# dtmf_rx.net
KiCad netlist of a schematic drawn in EAGLE
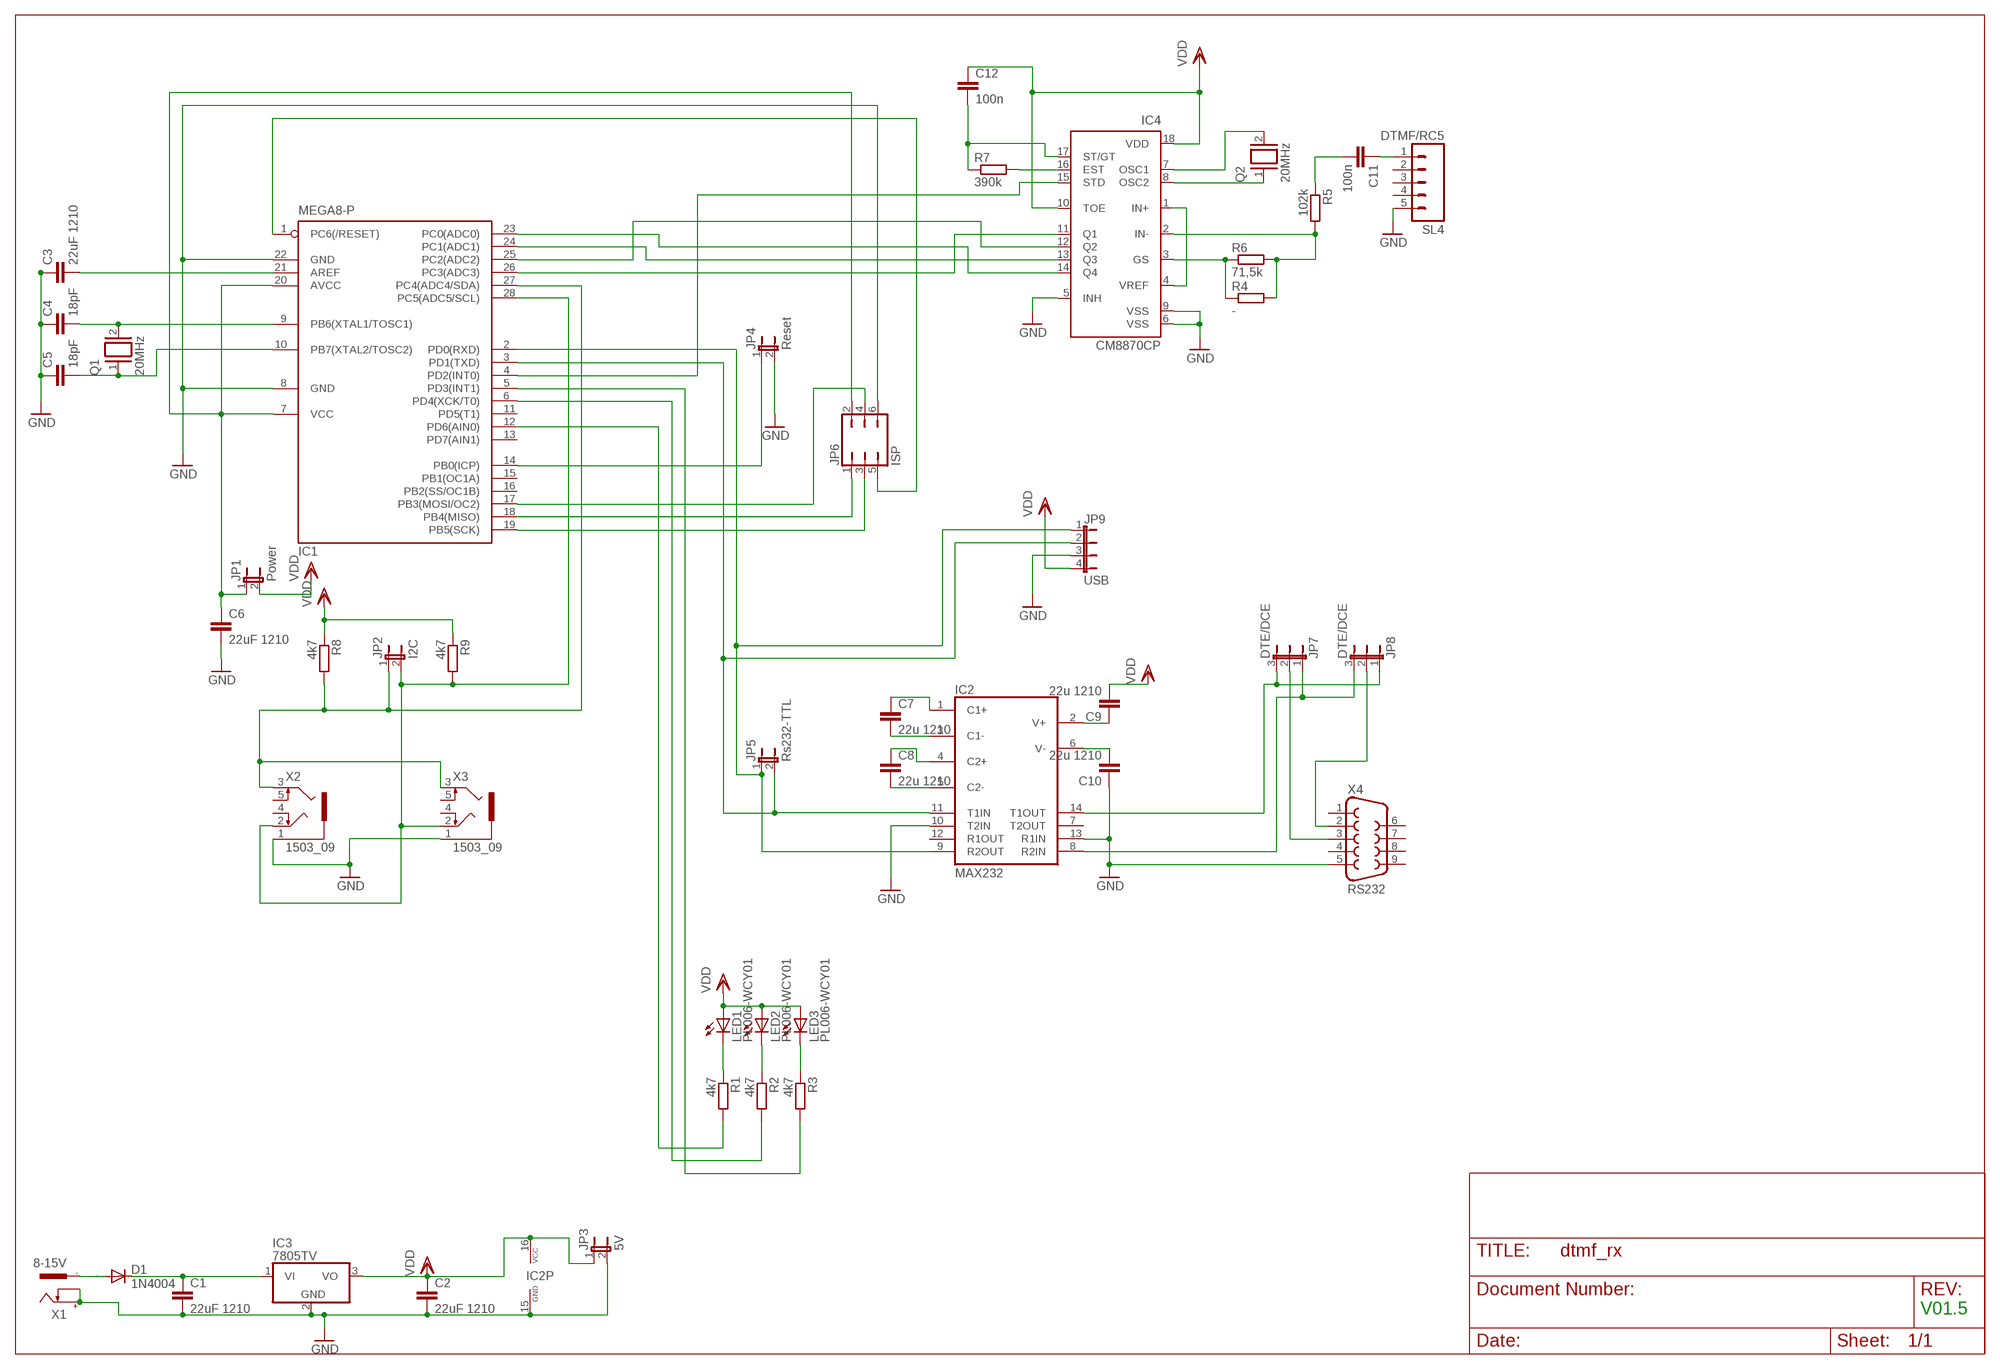
[diagram p0: schematic, sheet 1]

(export (version "E")
  (design (tool "Eeschema 10.0.6"))
  (components
    (comp (ref "C1")
      (value "22uF 1210")
      (footprint "eagle-import:C1206")
      (libsource (lib "eagle-import") (part "C-EUC1206"))
    )
    (comp (ref "C2")
      (value "22uF 1210")
      (footprint "eagle-import:C1206")
      (libsource (lib "eagle-import") (part "C-EUC1206"))
    )
    (comp (ref "C3")
      (value "22uF 1210")
      (footprint "eagle-import:C1206")
      (libsource (lib "eagle-import") (part "C-EUC1206"))
    )
    (comp (ref "C4")
      (value "18pF")
      (footprint "eagle-import:C025-025X050")
      (libsource (lib "eagle-import") (part "resistor_C-EU025-025X050"))
    )
    (comp (ref "C5")
      (value "18pF")
      (footprint "eagle-import:C025-025X050")
      (libsource (lib "eagle-import") (part "resistor_C-EU025-025X050"))
    )
    (comp (ref "C6")
      (value "22uF 1210")
      (footprint "eagle-import:C1206")
      (libsource (lib "eagle-import") (part "C-EUC1206"))
    )
    (comp (ref "C7")
      (value "22u 1210")
      (footprint "eagle-import:C1206")
      (libsource (lib "eagle-import") (part "C-EUC1206"))
    )
    (comp (ref "C8")
      (value "22u 1210")
      (footprint "eagle-import:C1206")
      (libsource (lib "eagle-import") (part "C-EUC1206"))
    )
    (comp (ref "C9")
      (value "22u 1210")
      (footprint "eagle-import:C1206")
      (libsource (lib "eagle-import") (part "C-EUC1206"))
    )
    (comp (ref "C10")
      (value "22u 1210")
      (footprint "eagle-import:C1206")
      (libsource (lib "eagle-import") (part "C-EUC1206"))
    )
    (comp (ref "C11")
      (value "100n")
      (footprint "eagle-import:C050-025X075")
      (libsource (lib "eagle-import") (part "C-EU050-025X075"))
    )
    (comp (ref "C12")
      (value "100n")
      (footprint "eagle-import:C050-025X075")
      (libsource (lib "eagle-import") (part "C-EU050-025X075"))
    )
    (comp (ref "D1")
      (value "1N4004")
      (footprint "eagle-import:DO41-10")
      (libsource (lib "eagle-import") (part "1N4004"))
    )
    (comp (ref "IC1")
      (value "MEGA8-P")
      (footprint "eagle-import:DIL28-3")
      (libsource (lib "eagle-import") (part "MEGA8-P"))
    )
    (comp (ref "IC2")
      (value "MAX232")
      (footprint "eagle-import:DIL16")
      (fields (field (name "MF") "MAXIM") (field (name "MPN") "MAX232ACPE+"))
      (libsource (lib "eagle-import") (part "MAX232"))
    )
    (comp (ref "IC3")
      (value "7805TV")
      (footprint "eagle-import:TO220V")
      (libsource (lib "eagle-import") (part "78TV05"))
    )
    (comp (ref "IC4")
      (value "CM8870CP")
      (footprint "eagle-import:DIL18")
      (libsource (lib "eagle-import") (part "CM8870CP"))
    )
    (comp (ref "JP1")
      (value "Power")
      (footprint "eagle-import:JP1")
      (libsource (lib "eagle-import") (part "JP1E"))
    )
    (comp (ref "JP2")
      (value "I2C")
      (footprint "eagle-import:JP1")
      (libsource (lib "eagle-import") (part "JP1E"))
    )
    (comp (ref "JP3")
      (value "5V")
      (footprint "eagle-import:JP1")
      (libsource (lib "eagle-import") (part "JP1E"))
    )
    (comp (ref "JP4")
      (value "Reset")
      (footprint "eagle-import:JP1")
      (libsource (lib "eagle-import") (part "JP1E"))
    )
    (comp (ref "JP5")
      (value "Rs232-TTL")
      (footprint "eagle-import:JP1")
      (libsource (lib "eagle-import") (part "JP1E"))
    )
    (comp (ref "JP6")
      (value "ISP")
      (footprint "eagle-import:JP3Q")
      (libsource (lib "eagle-import") (part "JP3Q"))
    )
    (comp (ref "JP7")
      (value "DTE/DCE")
      (footprint "eagle-import:JP2")
      (libsource (lib "eagle-import") (part "JP2E"))
    )
    (comp (ref "JP8")
      (value "DTE/DCE")
      (footprint "eagle-import:JP2")
      (libsource (lib "eagle-import") (part "JP2E"))
    )
    (comp (ref "JP9")
      (value "USB")
      (footprint "eagle-import:JP4")
      (libsource (lib "eagle-import") (part "JP4E"))
    )
    (comp (ref "LED1")
      (value "PL006-WCY01")
      (footprint "eagle-import:SOT23")
      (libsource (lib "eagle-import") (part "PL006-WCY01"))
    )
    (comp (ref "LED2")
      (value "PL006-WCY01")
      (footprint "eagle-import:SOT23")
      (libsource (lib "eagle-import") (part "PL006-WCY01"))
    )
    (comp (ref "LED3")
      (value "PL006-WCY01")
      (footprint "eagle-import:SOT23")
      (libsource (lib "eagle-import") (part "PL006-WCY01"))
    )
    (comp (ref "Q1")
      (value "20MHz")
      (footprint "eagle-import:QS")
      (libsource (lib "eagle-import") (part "XTAL/S"))
    )
    (comp (ref "Q2")
      (value "20MHz")
      (footprint "eagle-import:QS")
      (libsource (lib "eagle-import") (part "XTAL/S"))
    )
    (comp (ref "R1")
      (value "4k7")
      (footprint "eagle-import:0207_5V")
      (libsource (lib "eagle-import") (part "R-EU_0207/5V"))
    )
    (comp (ref "R2")
      (value "4k7")
      (footprint "eagle-import:0207_5V")
      (libsource (lib "eagle-import") (part "R-EU_0207/5V"))
    )
    (comp (ref "R3")
      (value "4k7")
      (footprint "eagle-import:0207_5V")
      (libsource (lib "eagle-import") (part "R-EU_0207/5V"))
    )
    (comp (ref "R4")
      (value "-")
      (footprint "eagle-import:0207_5V")
      (libsource (lib "eagle-import") (part "R-EU_0207/5V"))
    )
    (comp (ref "R5")
      (value "102k")
      (footprint "eagle-import:0207_5V")
      (libsource (lib "eagle-import") (part "R-EU_0207/5V"))
    )
    (comp (ref "R6")
      (value "71,5k")
      (footprint "eagle-import:0207_5V")
      (libsource (lib "eagle-import") (part "R-EU_0207/5V"))
    )
    (comp (ref "R7")
      (value "390k")
      (footprint "eagle-import:0207_5V")
      (libsource (lib "eagle-import") (part "R-EU_0207/5V"))
    )
    (comp (ref "R8")
      (value "4k7")
      (footprint "eagle-import:0207_5V")
      (libsource (lib "eagle-import") (part "R-EU_0207/5V"))
    )
    (comp (ref "R9")
      (value "4k7")
      (footprint "eagle-import:0207_5V")
      (libsource (lib "eagle-import") (part "R-EU_0207/5V"))
    )
    (comp (ref "SL4")
      (value "DTMF/RC5")
      (footprint "eagle-import:05P")
      (libsource (lib "eagle-import") (part "M05"))
    )
    (comp (ref "X1")
      (value "8-15V")
      (footprint "eagle-import:737992-5")
      (libsource (lib "eagle-import") (part "737992-55"))
    )
    (comp (ref "X2")
      (value "1503_09")
      (footprint "eagle-import:1503_09")
      (libsource (lib "eagle-import") (part "1503_09"))
    )
    (comp (ref "X3")
      (value "1503_09")
      (footprint "eagle-import:1503_09")
      (libsource (lib "eagle-import") (part "1503_09"))
    )
    (comp (ref "X4")
      (value "RS232")
      (footprint "eagle-import:F09H")
      (libsource (lib "eagle-import") (part "F09H"))
    )
  )
  (nets
    (net (code "1") (name "GND") (class "Default")
      (node (ref "C1") (pin "2") (pinfunction "2_2") (pintype "passive"))
      (node (ref "C10") (pin "1") (pinfunction "1_1") (pintype "passive"))
      (node (ref "C2") (pin "2") (pinfunction "2_2") (pintype "passive"))
      (node (ref "C3") (pin "1") (pinfunction "1_1") (pintype "passive"))
      (node (ref "C4") (pin "1") (pinfunction "1_1") (pintype "passive"))
      (node (ref "C5") (pin "1") (pinfunction "1_1") (pintype "passive"))
      (node (ref "C6") (pin "2") (pinfunction "2_2") (pintype "passive"))
      (node (ref "IC1") (pin "22") (pinfunction "GND_22") (pintype "power_in"))
      (node (ref "IC1") (pin "8") (pinfunction "GND_8") (pintype "power_in"))
      (node (ref "IC2") (pin "10") (pinfunction "T2IN_10") (pintype "input"))
      (node (ref "IC2") (pin "13") (pinfunction "R1IN_13") (pintype "input"))
      (node (ref "IC2") (pin "15") (pinfunction "GND_15") (pintype "power_in"))
      (node (ref "IC3") (pin "2") (pinfunction "GND_2") (pintype "passive"))
      (node (ref "IC4") (pin "5") (pinfunction "INH_5") (pintype "input"))
      (node (ref "IC4") (pin "6") (pinfunction "VSS_6") (pintype "power_in"))
      (node (ref "IC4") (pin "9") (pinfunction "VSS_9") (pintype "power_in"))
      (node (ref "JP3") (pin "2") (pinfunction "2_2") (pintype "passive"))
      (node (ref "JP4") (pin "2") (pinfunction "2_2") (pintype "passive"))
      (node (ref "JP6") (pin "6") (pinfunction "6_6") (pintype "passive"))
      (node (ref "JP9") (pin "3") (pinfunction "3_3") (pintype "passive"))
      (node (ref "SL4") (pin "5") (pinfunction "5_5") (pintype "passive"))
      (node (ref "X1") (pin "+") (pinfunction "+_+") (pintype "passive"))
      (node (ref "X1") (pin "K") (pinfunction "K_K") (pintype "passive"))
      (node (ref "X2") (pin "1") (pinfunction "1_1") (pintype "passive"))
      (node (ref "X3") (pin "1") (pinfunction "1_1") (pintype "passive"))
      (node (ref "X4") (pin "5") (pinfunction "5_5") (pintype "passive"))
    )
    (net (code "2") (name "Net-(C11-Pad1)") (class "Default")
      (node (ref "C11") (pin "1") (pinfunction "1_1") (pintype "passive"))
      (node (ref "SL4") (pin "1") (pinfunction "1_1") (pintype "passive"))
    )
    (net (code "3") (name "Net-(C11-Pad2)") (class "Default")
      (node (ref "C11") (pin "2") (pinfunction "2_2") (pintype "passive"))
      (node (ref "R5") (pin "1") (pinfunction "1_1") (pintype "passive"))
    )
    (net (code "4") (name "Net-(D1-PadA)") (class "Default")
      (node (ref "D1") (pin "A") (pinfunction "A_A") (pintype "passive"))
      (node (ref "X1") (pin "-1") (pinfunction "-1_-1") (pintype "passive"))
    )
    (net (code "5") (name "Net-(IC1-AREF)") (class "Default")
      (node (ref "C3") (pin "2") (pinfunction "2_2") (pintype "passive"))
      (node (ref "IC1") (pin "21") (pinfunction "AREF_21") (pintype "passive"))
    )
    (net (code "6") (name "Net-(IC1-AVCC)") (class "Default")
      (node (ref "C6") (pin "1") (pinfunction "1_1") (pintype "passive"))
      (node (ref "IC1") (pin "20") (pinfunction "AVCC_20") (pintype "power_in"))
      (node (ref "IC1") (pin "7") (pinfunction "VCC_7") (pintype "power_in"))
      (node (ref "JP1") (pin "1") (pinfunction "1_1") (pintype "passive"))
      (node (ref "JP6") (pin "2") (pinfunction "2_2") (pintype "passive"))
    )
    (net (code "7") (name "Net-(IC1-PB0(ICP))") (class "Default")
      (node (ref "IC1") (pin "14") (pinfunction "PB0(ICP)_14") (pintype "bidirectional"))
      (node (ref "JP4") (pin "1") (pinfunction "1_1") (pintype "passive"))
    )
    (net (code "8") (name "Net-(IC1-PB3(MOSI{slash}OC2))") (class "Default")
      (node (ref "IC1") (pin "17") (pinfunction "PB3(MOSI/OC2)_17") (pintype "bidirectional"))
      (node (ref "JP6") (pin "4") (pinfunction "4_4") (pintype "passive"))
    )
    (net (code "9") (name "Net-(IC1-PB4(MISO))") (class "Default")
      (node (ref "IC1") (pin "18") (pinfunction "PB4(MISO)_18") (pintype "bidirectional"))
      (node (ref "JP6") (pin "1") (pinfunction "1_1") (pintype "passive"))
    )
    (net (code "10") (name "Net-(IC1-PB5(SCK))") (class "Default")
      (node (ref "IC1") (pin "19") (pinfunction "PB5(SCK)_19") (pintype "bidirectional"))
      (node (ref "JP6") (pin "3") (pinfunction "3_3") (pintype "passive"))
    )
    (net (code "11") (name "Net-(IC1-PB6(XTAL1{slash}TOSC1))") (class "Default")
      (node (ref "C4") (pin "2") (pinfunction "2_2") (pintype "passive"))
      (node (ref "IC1") (pin "9") (pinfunction "PB6(XTAL1/TOSC1)_9") (pintype "bidirectional"))
      (node (ref "Q1") (pin "2") (pinfunction "2_2") (pintype "passive"))
    )
    (net (code "12") (name "Net-(IC1-PB7(XTAL2{slash}TOSC2))") (class "Default")
      (node (ref "C5") (pin "2") (pinfunction "2_2") (pintype "passive"))
      (node (ref "IC1") (pin "10") (pinfunction "PB7(XTAL2/TOSC2)_10") (pintype "bidirectional"))
      (node (ref "Q1") (pin "1") (pinfunction "1_1") (pintype "passive"))
    )
    (net (code "13") (name "Net-(IC1-PC0(ADC0))") (class "Default")
      (node (ref "IC1") (pin "23") (pinfunction "PC0(ADC0)_23") (pintype "bidirectional"))
      (node (ref "IC4") (pin "14") (pinfunction "Q4_14") (pintype "output"))
    )
    (net (code "14") (name "Net-(IC1-PC1(ADC1))") (class "Default")
      (node (ref "IC1") (pin "24") (pinfunction "PC1(ADC1)_24") (pintype "bidirectional"))
      (node (ref "IC4") (pin "13") (pinfunction "Q3_13") (pintype "output"))
    )
    (net (code "15") (name "Net-(IC1-PC2(ADC2))") (class "Default")
      (node (ref "IC1") (pin "25") (pinfunction "PC2(ADC2)_25") (pintype "bidirectional"))
      (node (ref "IC4") (pin "12") (pinfunction "Q2_12") (pintype "output"))
    )
    (net (code "16") (name "Net-(IC1-PC3(ADC3))") (class "Default")
      (node (ref "IC1") (pin "26") (pinfunction "PC3(ADC3)_26") (pintype "bidirectional"))
      (node (ref "IC4") (pin "11") (pinfunction "Q1_11") (pintype "output"))
    )
    (net (code "17") (name "Net-(IC1-PC4(ADC4{slash}SDA))") (class "Default")
      (node (ref "IC1") (pin "27") (pinfunction "PC4(ADC4/SDA)_27") (pintype "bidirectional"))
      (node (ref "JP2") (pin "1") (pinfunction "1_1") (pintype "passive"))
      (node (ref "R8") (pin "2") (pinfunction "2_2") (pintype "passive"))
      (node (ref "X2") (pin "3") (pinfunction "3_3") (pintype "passive"))
      (node (ref "X3") (pin "3") (pinfunction "3_3") (pintype "passive"))
    )
    (net (code "18") (name "Net-(IC1-PC5(ADC5{slash}SCL))") (class "Default")
      (node (ref "IC1") (pin "28") (pinfunction "PC5(ADC5/SCL)_28") (pintype "bidirectional"))
      (node (ref "JP2") (pin "2") (pinfunction "2_2") (pintype "passive"))
      (node (ref "R9") (pin "2") (pinfunction "2_2") (pintype "passive"))
      (node (ref "X2") (pin "2") (pinfunction "2_2") (pintype "passive"))
      (node (ref "X3") (pin "2") (pinfunction "2_2") (pintype "passive"))
    )
    (net (code "19") (name "Net-(IC1-PC6({slash}RESET))") (class "Default")
      (node (ref "IC1") (pin "1") (pinfunction "PC6(/RESET)_1") (pintype "bidirectional"))
      (node (ref "JP6") (pin "5") (pinfunction "5_5") (pintype "passive"))
    )
    (net (code "20") (name "Net-(IC1-PD0(RXD))") (class "Default")
      (node (ref "IC1") (pin "2") (pinfunction "PD0(RXD)_2") (pintype "bidirectional"))
      (node (ref "IC2") (pin "9") (pinfunction "R2OUT_9") (pintype "output"))
      (node (ref "JP5") (pin "1") (pinfunction "1_1") (pintype "passive"))
      (node (ref "JP9") (pin "1") (pinfunction "1_1") (pintype "passive"))
    )
    (net (code "21") (name "Net-(IC1-PD1(TXD))") (class "Default")
      (node (ref "IC1") (pin "3") (pinfunction "PD1(TXD)_3") (pintype "bidirectional"))
      (node (ref "IC2") (pin "11") (pinfunction "T1IN_11") (pintype "input"))
      (node (ref "JP5") (pin "2") (pinfunction "2_2") (pintype "passive"))
      (node (ref "JP9") (pin "2") (pinfunction "2_2") (pintype "passive"))
    )
    (net (code "22") (name "Net-(IC1-PD2(INT0))") (class "Default")
      (node (ref "IC1") (pin "4") (pinfunction "PD2(INT0)_4") (pintype "bidirectional"))
      (node (ref "IC4") (pin "15") (pinfunction "STD_15") (pintype "input"))
    )
    (net (code "23") (name "Net-(IC1-PD3(INT1))") (class "Default")
      (node (ref "IC1") (pin "5") (pinfunction "PD3(INT1)_5") (pintype "bidirectional"))
      (node (ref "R3") (pin "2") (pinfunction "2_2") (pintype "passive"))
    )
    (net (code "24") (name "Net-(IC1-PD4(XCK{slash}T0))") (class "Default")
      (node (ref "IC1") (pin "6") (pinfunction "PD4(XCK/T0)_6") (pintype "bidirectional"))
      (node (ref "R2") (pin "2") (pinfunction "2_2") (pintype "passive"))
    )
    (net (code "25") (name "Net-(IC1-PD6(AIN0))") (class "Default")
      (node (ref "IC1") (pin "12") (pinfunction "PD6(AIN0)_12") (pintype "bidirectional"))
      (node (ref "R1") (pin "2") (pinfunction "2_2") (pintype "passive"))
    )
    (net (code "26") (name "Net-(IC2A-C1+)") (class "Default")
      (node (ref "C7") (pin "1") (pinfunction "1_1") (pintype "passive"))
      (node (ref "IC2") (pin "1") (pinfunction "C1+_1") (pintype "bidirectional"))
    )
    (net (code "27") (name "Net-(IC2A-C1-)") (class "Default")
      (node (ref "C7") (pin "2") (pinfunction "2_2") (pintype "passive"))
      (node (ref "IC2") (pin "3") (pinfunction "C1-_3") (pintype "bidirectional"))
    )
    (net (code "28") (name "Net-(IC2A-C2+)") (class "Default")
      (node (ref "C8") (pin "1") (pinfunction "1_1") (pintype "passive"))
      (node (ref "IC2") (pin "4") (pinfunction "C2+_4") (pintype "bidirectional"))
    )
    (net (code "29") (name "Net-(IC2A-C2-)") (class "Default")
      (node (ref "C8") (pin "2") (pinfunction "2_2") (pintype "passive"))
      (node (ref "IC2") (pin "5") (pinfunction "C2-_5") (pintype "bidirectional"))
    )
    (net (code "30") (name "Net-(IC2A-R2IN)") (class "Default")
      (node (ref "IC2") (pin "8") (pinfunction "R2IN_8") (pintype "input"))
      (node (ref "JP7") (pin "1") (pinfunction "1_1") (pintype "passive"))
      (node (ref "JP8") (pin "3") (pinfunction "3_3") (pintype "passive"))
    )
    (net (code "31") (name "Net-(IC2A-T1OUT)") (class "Default")
      (node (ref "IC2") (pin "14") (pinfunction "T1OUT_14") (pintype "output"))
      (node (ref "JP7") (pin "3") (pinfunction "3_3") (pintype "passive"))
      (node (ref "JP8") (pin "1") (pinfunction "1_1") (pintype "passive"))
    )
    (net (code "32") (name "Net-(IC2A-V+)") (class "Default")
      (node (ref "C9") (pin "1") (pinfunction "1_1") (pintype "passive"))
      (node (ref "IC2") (pin "2") (pinfunction "V+_2") (pintype "bidirectional"))
    )
    (net (code "33") (name "Net-(IC2A-V-)") (class "Default")
      (node (ref "C10") (pin "2") (pinfunction "2_2") (pintype "passive"))
      (node (ref "IC2") (pin "6") (pinfunction "V-_6") (pintype "bidirectional"))
    )
    (net (code "34") (name "Net-(IC3-VI)") (class "Default")
      (node (ref "C1") (pin "1") (pinfunction "1_1") (pintype "passive"))
      (node (ref "D1") (pin "C") (pinfunction "C_C") (pintype "passive"))
      (node (ref "IC3") (pin "1") (pinfunction "VI_1") (pintype "input"))
    )
    (net (code "35") (name "Net-(IC4-EST)") (class "Default")
      (node (ref "IC4") (pin "16") (pinfunction "EST_16") (pintype "input"))
      (node (ref "R7") (pin "2") (pinfunction "2_2") (pintype "passive"))
    )
    (net (code "36") (name "Net-(IC4-GS)") (class "Default")
      (node (ref "IC4") (pin "3") (pinfunction "GS_3") (pintype "input"))
      (node (ref "R4") (pin "1") (pinfunction "1_1") (pintype "passive"))
      (node (ref "R6") (pin "1") (pinfunction "1_1") (pintype "passive"))
    )
    (net (code "37") (name "Net-(IC4-IN+)") (class "Default")
      (node (ref "IC4") (pin "1") (pinfunction "IN+_1") (pintype "input"))
      (node (ref "IC4") (pin "4") (pinfunction "VREF_4") (pintype "output"))
    )
    (net (code "38") (name "Net-(IC4-IN-)") (class "Default")
      (node (ref "IC4") (pin "2") (pinfunction "IN-_2") (pintype "input"))
      (node (ref "R4") (pin "2") (pinfunction "2_2") (pintype "passive"))
      (node (ref "R5") (pin "2") (pinfunction "2_2") (pintype "passive"))
      (node (ref "R6") (pin "2") (pinfunction "2_2") (pintype "passive"))
    )
    (net (code "39") (name "Net-(IC4-OSC1)") (class "Default")
      (node (ref "IC4") (pin "7") (pinfunction "OSC1_7") (pintype "input"))
      (node (ref "Q2") (pin "2") (pinfunction "2_2") (pintype "passive"))
    )
    (net (code "40") (name "Net-(IC4-OSC2)") (class "Default")
      (node (ref "IC4") (pin "8") (pinfunction "OSC2_8") (pintype "bidirectional"))
      (node (ref "Q2") (pin "1") (pinfunction "1_1") (pintype "passive"))
    )
    (net (code "41") (name "Net-(IC4-ST{slash}GT)") (class "Default")
      (node (ref "C12") (pin "2") (pinfunction "2_2") (pintype "passive"))
      (node (ref "IC4") (pin "17") (pinfunction "ST/GT_17") (pintype "bidirectional"))
      (node (ref "R7") (pin "1") (pinfunction "1_1") (pintype "passive"))
    )
    (net (code "42") (name "Net-(JP7-Pad2)") (class "Default")
      (node (ref "JP7") (pin "2") (pinfunction "2_2") (pintype "passive"))
      (node (ref "X4") (pin "3") (pinfunction "3_3") (pintype "passive"))
    )
    (net (code "43") (name "Net-(JP8-Pad2)") (class "Default")
      (node (ref "JP8") (pin "2") (pinfunction "2_2") (pintype "passive"))
      (node (ref "X4") (pin "2") (pinfunction "2_2") (pintype "passive"))
    )
    (net (code "44") (name "Net-(LED1-C)") (class "Default")
      (node (ref "LED1") (pin "3") (pinfunction "C_3") (pintype "passive"))
      (node (ref "R1") (pin "1") (pinfunction "1_1") (pintype "passive"))
    )
    (net (code "45") (name "Net-(LED2-C)") (class "Default")
      (node (ref "LED2") (pin "3") (pinfunction "C_3") (pintype "passive"))
      (node (ref "R2") (pin "1") (pinfunction "1_1") (pintype "passive"))
    )
    (net (code "46") (name "Net-(LED3-C)") (class "Default")
      (node (ref "LED3") (pin "3") (pinfunction "C_3") (pintype "passive"))
      (node (ref "R3") (pin "1") (pinfunction "1_1") (pintype "passive"))
    )
    (net (code "47") (name "VDD") (class "Default")
      (node (ref "C12") (pin "1") (pinfunction "1_1") (pintype "passive"))
      (node (ref "C2") (pin "1") (pinfunction "1_1") (pintype "passive"))
      (node (ref "C9") (pin "2") (pinfunction "2_2") (pintype "passive"))
      (node (ref "IC2") (pin "16") (pinfunction "VCC_16") (pintype "power_in"))
      (node (ref "IC3") (pin "3") (pinfunction "VO_3") (pintype "passive"))
      (node (ref "IC4") (pin "10") (pinfunction "TOE_10") (pintype "input"))
      (node (ref "IC4") (pin "18") (pinfunction "VDD_18") (pintype "power_in"))
      (node (ref "JP1") (pin "2") (pinfunction "2_2") (pintype "passive"))
      (node (ref "JP3") (pin "1") (pinfunction "1_1") (pintype "passive"))
      (node (ref "JP9") (pin "4") (pinfunction "4_4") (pintype "passive"))
      (node (ref "LED1") (pin "1") (pinfunction "A_1") (pintype "passive"))
      (node (ref "LED2") (pin "1") (pinfunction "A_1") (pintype "passive"))
      (node (ref "LED3") (pin "1") (pinfunction "A_1") (pintype "passive"))
      (node (ref "R8") (pin "1") (pinfunction "1_1") (pintype "passive"))
      (node (ref "R9") (pin "1") (pinfunction "1_1") (pintype "passive"))
    )
    (net (code "48") (name "unconnected-(IC1-PB1(OC1A)-Pad15)") (class "Default")
      (node (ref "IC1") (pin "15") (pinfunction "PB1(OC1A)_15") (pintype "bidirectional"))
    )
    (net (code "49") (name "unconnected-(IC1-PB2(SS{slash}OC1B)-Pad16)") (class "Default")
      (node (ref "IC1") (pin "16") (pinfunction "PB2(SS/OC1B)_16") (pintype "bidirectional"))
    )
    (net (code "50") (name "unconnected-(IC1-PD5(T1)-Pad11)") (class "Default")
      (node (ref "IC1") (pin "11") (pinfunction "PD5(T1)_11") (pintype "bidirectional"))
    )
    (net (code "51") (name "unconnected-(IC1-PD7(AIN1)-Pad13)") (class "Default")
      (node (ref "IC1") (pin "13") (pinfunction "PD7(AIN1)_13") (pintype "bidirectional"))
    )
    (net (code "52") (name "unconnected-(IC2A-R1OUT-Pad12)") (class "Default")
      (node (ref "IC2") (pin "12") (pinfunction "R1OUT_12") (pintype "output"))
    )
    (net (code "53") (name "unconnected-(IC2A-T2OUT-Pad7)") (class "Default")
      (node (ref "IC2") (pin "7") (pinfunction "T2OUT_7") (pintype "output"))
    )
    (net (code "54") (name "unconnected-(SL4-Pad2)") (class "Default")
      (node (ref "SL4") (pin "2") (pinfunction "2_2") (pintype "passive"))
    )
    (net (code "55") (name "unconnected-(SL4-Pad3)") (class "Default")
      (node (ref "SL4") (pin "3") (pinfunction "3_3") (pintype "passive"))
    )
    (net (code "56") (name "unconnected-(SL4-Pad4)") (class "Default")
      (node (ref "SL4") (pin "4") (pinfunction "4_4") (pintype "passive"))
    )
    (net (code "57") (name "unconnected-(X1-Pad-2)") (class "Default")
      (node (ref "X1") (pin "-2") (pinfunction "-2_-2") (pintype "passive"))
    )
    (net (code "58") (name "unconnected-(X2-Pad4)") (class "Default")
      (node (ref "X2") (pin "4") (pinfunction "4_4") (pintype "passive"))
    )
    (net (code "59") (name "unconnected-(X2-Pad5)") (class "Default")
      (node (ref "X2") (pin "5") (pinfunction "5_5") (pintype "passive"))
    )
    (net (code "60") (name "unconnected-(X3-Pad4)") (class "Default")
      (node (ref "X3") (pin "4") (pinfunction "4_4") (pintype "passive"))
    )
    (net (code "61") (name "unconnected-(X3-Pad5)") (class "Default")
      (node (ref "X3") (pin "5") (pinfunction "5_5") (pintype "passive"))
    )
    (net (code "62") (name "unconnected-(X4-Pad1)") (class "Default")
      (node (ref "X4") (pin "1") (pinfunction "1_1") (pintype "passive"))
    )
    (net (code "63") (name "unconnected-(X4-Pad4)") (class "Default")
      (node (ref "X4") (pin "4") (pinfunction "4_4") (pintype "passive"))
    )
    (net (code "64") (name "unconnected-(X4-Pad6)") (class "Default")
      (node (ref "X4") (pin "6") (pinfunction "6_6") (pintype "passive"))
    )
    (net (code "65") (name "unconnected-(X4-Pad7)") (class "Default")
      (node (ref "X4") (pin "7") (pinfunction "7_7") (pintype "passive"))
    )
    (net (code "66") (name "unconnected-(X4-Pad8)") (class "Default")
      (node (ref "X4") (pin "8") (pinfunction "8_8") (pintype "passive"))
    )
    (net (code "67") (name "unconnected-(X4-Pad9)") (class "Default")
      (node (ref "X4") (pin "9") (pinfunction "9_9") (pintype "passive"))
    )
  )
)
